# motor_controller.net
KiCad netlist of a schematic drawn in EAGLE
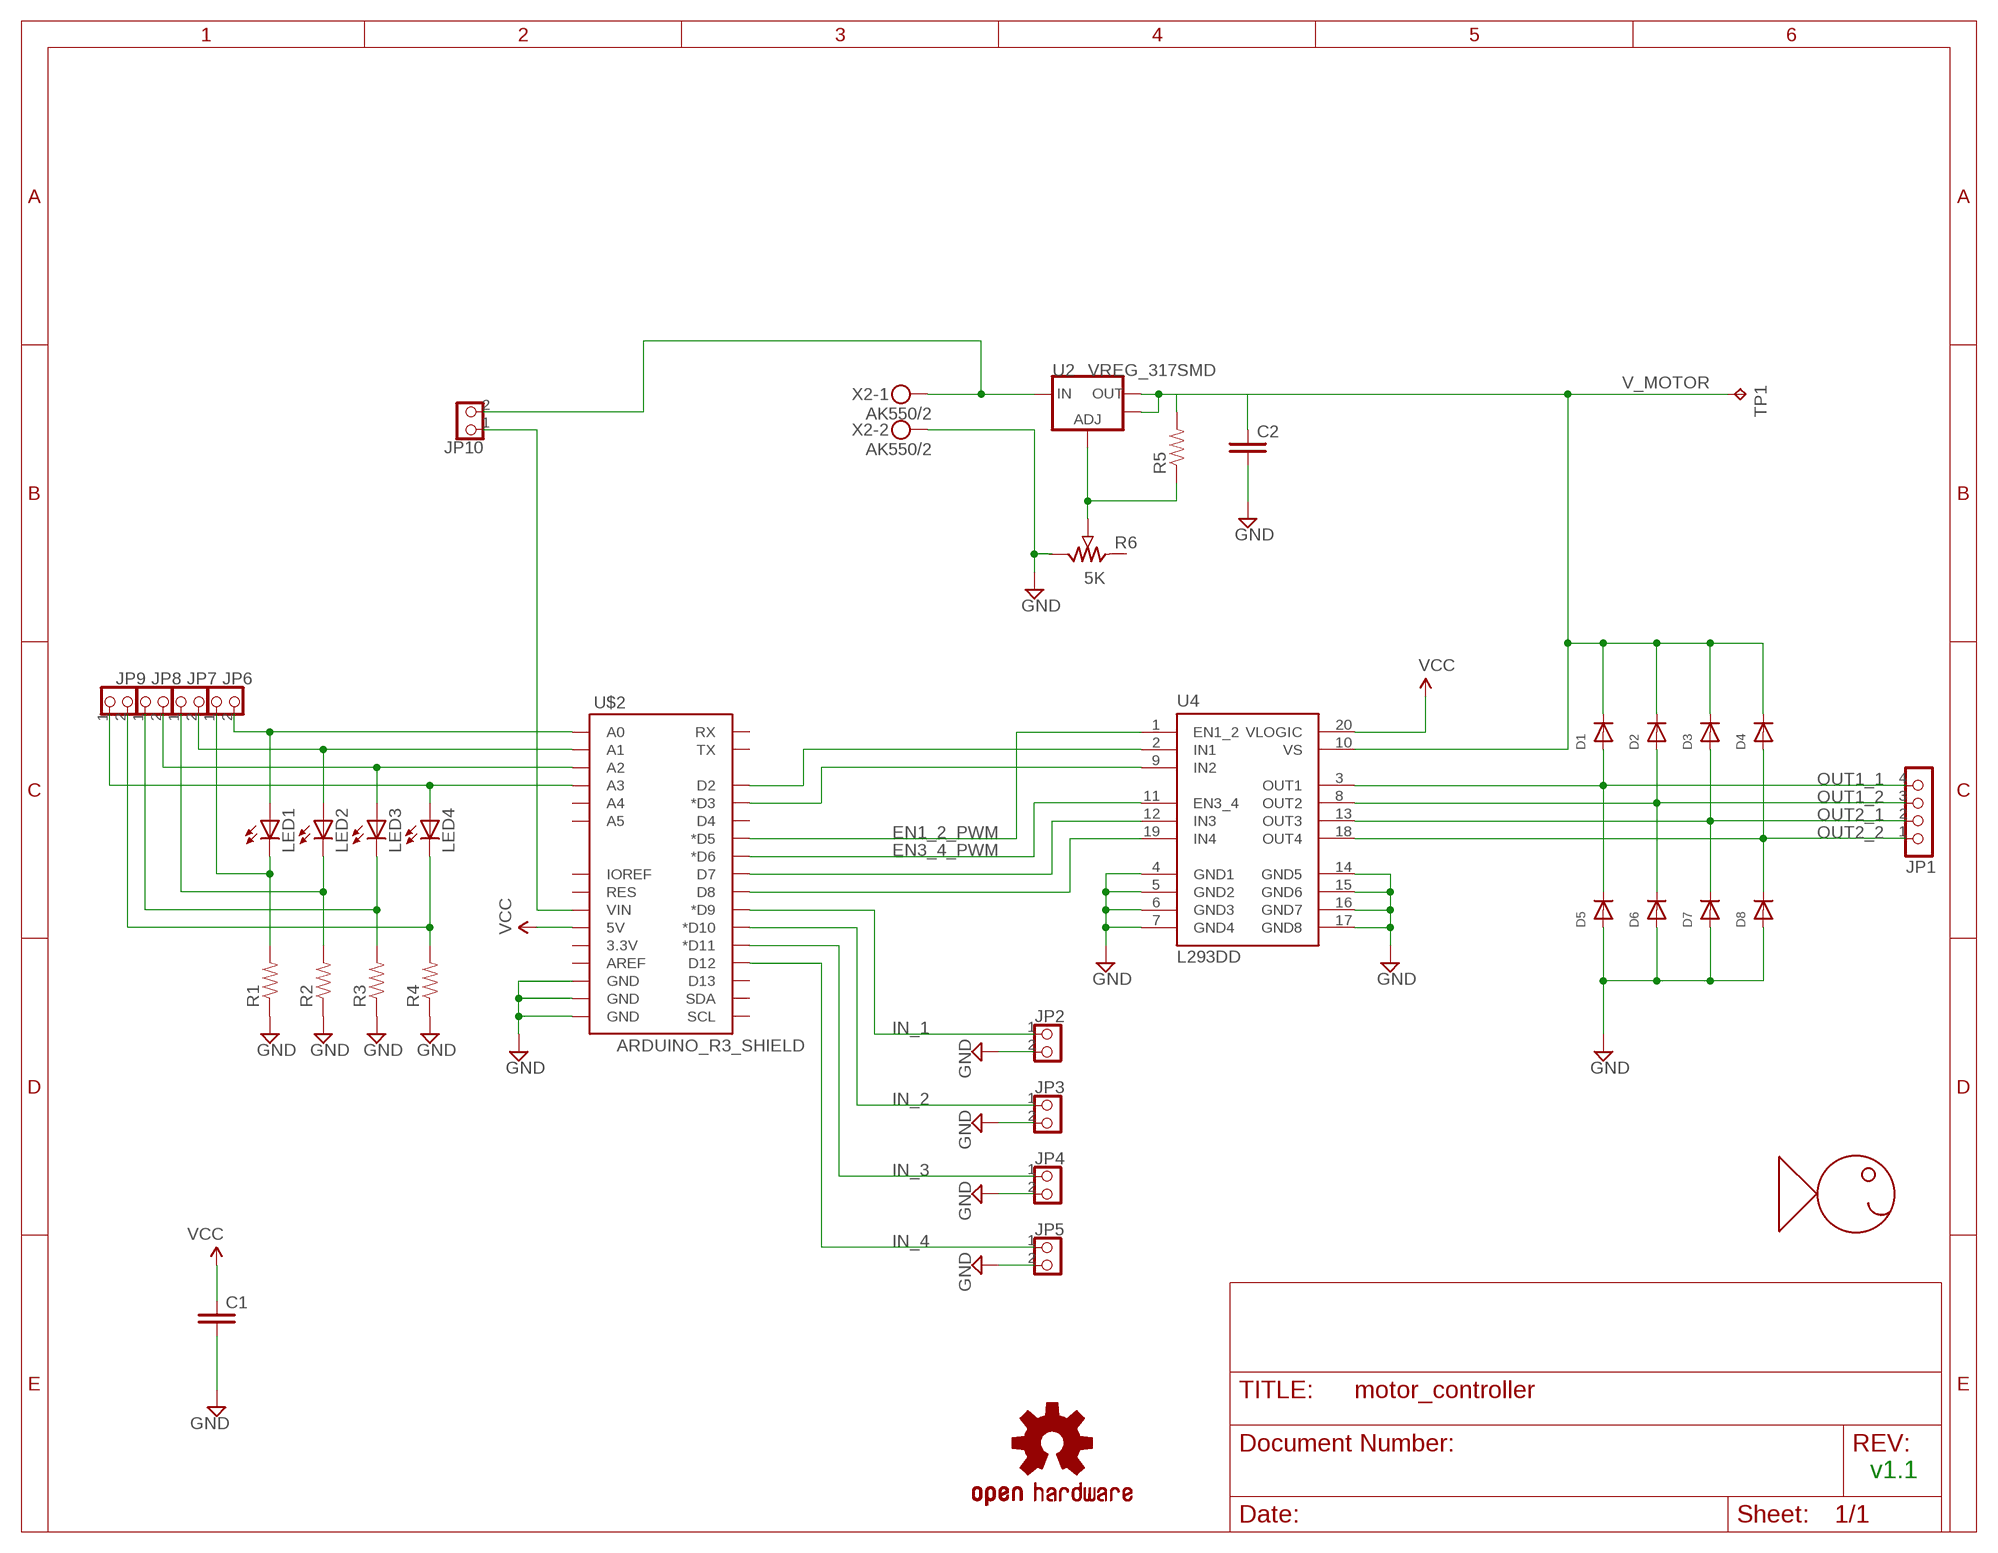
[diagram p0: schematic, sheet 1]

(export (version "E")
  (design (tool "Eeschema 10.0.6"))
  (components
    (comp (ref "C1")
      (value "CAPACITORC0603")
      (footprint "eagle-import:C0603")
      (libsource (lib "eagle-import") (part "CAPACITORC0603"))
    )
    (comp (ref "C2")
      (value "CAPACITORC0603")
      (footprint "eagle-import:C0603")
      (libsource (lib "eagle-import") (part "CAPACITORC0603"))
    )
    (comp (ref "D1")
      (value "DIODESOD-123")
      (footprint "eagle-import:SOD-123")
      (libsource (lib "eagle-import") (part "DIODESOD-123"))
    )
    (comp (ref "D2")
      (value "DIODESOD-123")
      (footprint "eagle-import:SOD-123")
      (libsource (lib "eagle-import") (part "DIODESOD-123"))
    )
    (comp (ref "D3")
      (value "DIODESOD-123")
      (footprint "eagle-import:SOD-123")
      (libsource (lib "eagle-import") (part "DIODESOD-123"))
    )
    (comp (ref "D4")
      (value "DIODESOD-123")
      (footprint "eagle-import:SOD-123")
      (libsource (lib "eagle-import") (part "DIODESOD-123"))
    )
    (comp (ref "D5")
      (value "DIODESOD-123")
      (footprint "eagle-import:SOD-123")
      (libsource (lib "eagle-import") (part "DIODESOD-123"))
    )
    (comp (ref "D6")
      (value "DIODESOD-123")
      (footprint "eagle-import:SOD-123")
      (libsource (lib "eagle-import") (part "DIODESOD-123"))
    )
    (comp (ref "D7")
      (value "DIODESOD-123")
      (footprint "eagle-import:SOD-123")
      (libsource (lib "eagle-import") (part "DIODESOD-123"))
    )
    (comp (ref "D8")
      (value "DIODESOD-123")
      (footprint "eagle-import:SOD-123")
      (libsource (lib "eagle-import") (part "DIODESOD-123"))
    )
    (comp (ref "JP1")
      (value "PINHD-1X4/90")
      (footprint "eagle-import:1X04_90")
      (libsource (lib "eagle-import") (part "PINHD-1X4/90"))
    )
    (comp (ref "JP2")
      (value "PINHD-1X2")
      (footprint "eagle-import:1X02")
      (libsource (lib "eagle-import") (part "PINHD-1X2"))
    )
    (comp (ref "JP3")
      (value "PINHD-1X2")
      (footprint "eagle-import:1X02")
      (libsource (lib "eagle-import") (part "PINHD-1X2"))
    )
    (comp (ref "JP4")
      (value "PINHD-1X2")
      (footprint "eagle-import:1X02")
      (libsource (lib "eagle-import") (part "PINHD-1X2"))
    )
    (comp (ref "JP5")
      (value "PINHD-1X2")
      (footprint "eagle-import:1X02")
      (libsource (lib "eagle-import") (part "PINHD-1X2"))
    )
    (comp (ref "JP6")
      (value "PINHD-1X2")
      (footprint "eagle-import:1X02")
      (libsource (lib "eagle-import") (part "PINHD-1X2"))
    )
    (comp (ref "JP7")
      (value "PINHD-1X2")
      (footprint "eagle-import:1X02")
      (libsource (lib "eagle-import") (part "PINHD-1X2"))
    )
    (comp (ref "JP8")
      (value "PINHD-1X2")
      (footprint "eagle-import:1X02")
      (libsource (lib "eagle-import") (part "PINHD-1X2"))
    )
    (comp (ref "JP9")
      (value "PINHD-1X2")
      (footprint "eagle-import:1X02")
      (libsource (lib "eagle-import") (part "PINHD-1X2"))
    )
    (comp (ref "JP10")
      (value "PINHD-1X2")
      (footprint "eagle-import:1X02")
      (libsource (lib "eagle-import") (part "PINHD-1X2"))
    )
    (comp (ref "LED1")
      (value "LED0805")
      (footprint "eagle-import:LED_0805")
      (libsource (lib "eagle-import") (part "LED0805"))
    )
    (comp (ref "LED2")
      (value "LED0805")
      (footprint "eagle-import:LED_0805")
      (libsource (lib "eagle-import") (part "LED0805"))
    )
    (comp (ref "LED3")
      (value "LED0805")
      (footprint "eagle-import:LED_0805")
      (libsource (lib "eagle-import") (part "LED0805"))
    )
    (comp (ref "LED4")
      (value "LED0805")
      (footprint "eagle-import:LED_0805")
      (libsource (lib "eagle-import") (part "LED0805"))
    )
    (comp (ref "LOGO1")
      (value "OSHW-LOGOM")
      (footprint "eagle-import:OSHW-LOGO-M")
      (libsource (lib "eagle-import") (part "OSHW-LOGOM"))
    )
    (comp (ref "R1")
      (value "RESISTOR_SMD0603-RES")
      (footprint "eagle-import:0603-RES")
      (libsource (lib "eagle-import") (part "RESISTOR_SMD0603-RES"))
    )
    (comp (ref "R2")
      (value "RESISTOR_SMD0603-RES")
      (footprint "eagle-import:0603-RES")
      (libsource (lib "eagle-import") (part "RESISTOR_SMD0603-RES"))
    )
    (comp (ref "R3")
      (value "RESISTOR_SMD0603-RES")
      (footprint "eagle-import:0603-RES")
      (libsource (lib "eagle-import") (part "RESISTOR_SMD0603-RES"))
    )
    (comp (ref "R4")
      (value "RESISTOR_SMD0603-RES")
      (footprint "eagle-import:0603-RES")
      (libsource (lib "eagle-import") (part "RESISTOR_SMD0603-RES"))
    )
    (comp (ref "R5")
      (value "RESISTOR_SMD0603-RES")
      (footprint "eagle-import:0603-RES")
      (libsource (lib "eagle-import") (part "RESISTOR_SMD0603-RES"))
    )
    (comp (ref "R6")
      (value "5K")
      (footprint "eagle-import:BOURNS_3362H")
      (libsource (lib "eagle-import") (part "POTBOURNS_3362H"))
    )
    (comp (ref "TP1")
      (value "TEST_POINTPAD1-20")
      (footprint "eagle-import:P1-20")
      (libsource (lib "eagle-import") (part "TEST_POINTPAD1-20"))
    )
    (comp (ref "U$1")
      (value "FHI_LOGO")
      (footprint "eagle-import:FHI_LOGO")
      (libsource (lib "eagle-import") (part "FHI_LOGO"))
    )
    (comp (ref "U$2")
      (value "ARDUINO_R3_SHIELD")
      (footprint "eagle-import:UNO_R3_SHIELD")
      (libsource (lib "eagle-import") (part "ARDUINO_R3_SHIELD"))
    )
    (comp (ref "U2")
      (value "VREG_317SMD")
      (footprint "eagle-import:SOT223")
      (libsource (lib "eagle-import") (part "VREG_317SMD"))
    )
    (comp (ref "U4")
      (value "L293DD")
      (footprint "eagle-import:SO20")
      (libsource (lib "eagle-import") (part "L293DD"))
    )
    (comp (ref "X2")
      (value "AK550/2")
      (footprint "eagle-import:AK550_2")
      (libsource (lib "eagle-import") (part "AK550/2"))
    )
  )
  (nets
    (net (code "1") (name "/EN1_2_PWM") (class "Default")
      (node (ref "U$2") (pin "D5") (pinfunction "*D5_D5") (pintype "bidirectional"))
      (node (ref "U4") (pin "1") (pinfunction "EN1_2_1") (pintype "input"))
    )
    (net (code "2") (name "/EN3_4_PWM") (class "Default")
      (node (ref "U$2") (pin "D6") (pinfunction "*D6_D6") (pintype "bidirectional"))
      (node (ref "U4") (pin "11") (pinfunction "EN3_4_11") (pintype "input"))
    )
    (net (code "3") (name "/IN_1") (class "Default")
      (node (ref "JP2") (pin "1") (pinfunction "1_1") (pintype "passive"))
      (node (ref "U$2") (pin "D9") (pinfunction "*D9_D9") (pintype "bidirectional"))
    )
    (net (code "4") (name "/IN_2") (class "Default")
      (node (ref "JP3") (pin "1") (pinfunction "1_1") (pintype "passive"))
      (node (ref "U$2") (pin "D10") (pinfunction "*D10_D10") (pintype "bidirectional"))
    )
    (net (code "5") (name "/IN_3") (class "Default")
      (node (ref "JP4") (pin "1") (pinfunction "1_1") (pintype "passive"))
      (node (ref "U$2") (pin "D11") (pinfunction "*D11_D11") (pintype "bidirectional"))
    )
    (net (code "6") (name "/IN_4") (class "Default")
      (node (ref "JP5") (pin "1") (pinfunction "1_1") (pintype "passive"))
      (node (ref "U$2") (pin "D12") (pinfunction "D12_D12") (pintype "bidirectional"))
    )
    (net (code "7") (name "/OUT1_1") (class "Default")
      (node (ref "D1") (pin "A") (pinfunction "A_A") (pintype "passive"))
      (node (ref "D5") (pin "C") (pinfunction "C_C") (pintype "passive"))
      (node (ref "JP1") (pin "4") (pinfunction "4_4") (pintype "passive"))
      (node (ref "U4") (pin "3") (pinfunction "OUT1_3") (pintype "output"))
    )
    (net (code "8") (name "/OUT1_2") (class "Default")
      (node (ref "D2") (pin "A") (pinfunction "A_A") (pintype "passive"))
      (node (ref "D6") (pin "C") (pinfunction "C_C") (pintype "passive"))
      (node (ref "JP1") (pin "3") (pinfunction "3_3") (pintype "passive"))
      (node (ref "U4") (pin "8") (pinfunction "OUT2_8") (pintype "output"))
    )
    (net (code "9") (name "/OUT2_1") (class "Default")
      (node (ref "D3") (pin "A") (pinfunction "A_A") (pintype "passive"))
      (node (ref "D7") (pin "C") (pinfunction "C_C") (pintype "passive"))
      (node (ref "JP1") (pin "2") (pinfunction "2_2") (pintype "passive"))
      (node (ref "U4") (pin "13") (pinfunction "OUT3_13") (pintype "output"))
    )
    (net (code "10") (name "/OUT2_2") (class "Default")
      (node (ref "D4") (pin "A") (pinfunction "A_A") (pintype "passive"))
      (node (ref "D8") (pin "C") (pinfunction "C_C") (pintype "passive"))
      (node (ref "JP1") (pin "1") (pinfunction "1_1") (pintype "passive"))
      (node (ref "U4") (pin "18") (pinfunction "OUT4_18") (pintype "output"))
    )
    (net (code "11") (name "/V_MOTOR") (class "Default")
      (node (ref "C2") (pin "1") (pinfunction "1_1") (pintype "passive"))
      (node (ref "D1") (pin "C") (pinfunction "C_C") (pintype "passive"))
      (node (ref "D2") (pin "C") (pinfunction "C_C") (pintype "passive"))
      (node (ref "D3") (pin "C") (pinfunction "C_C") (pintype "passive"))
      (node (ref "D4") (pin "C") (pinfunction "C_C") (pintype "passive"))
      (node (ref "R5") (pin "2") (pinfunction "2_2") (pintype "passive"))
      (node (ref "TP1") (pin "TP") (pinfunction "TP_TP") (pintype "input"))
      (node (ref "U2") (pin "2") (pinfunction "OUT1_2") (pintype "output"))
      (node (ref "U2") (pin "4") (pinfunction "OUT2_4") (pintype "output"))
      (node (ref "U4") (pin "10") (pinfunction "VS_10") (pintype "power_in"))
    )
    (net (code "12") (name "GND") (class "Default")
      (node (ref "C1") (pin "2") (pinfunction "2_2") (pintype "passive"))
      (node (ref "C2") (pin "2") (pinfunction "2_2") (pintype "passive"))
      (node (ref "D5") (pin "A") (pinfunction "A_A") (pintype "passive"))
      (node (ref "D6") (pin "A") (pinfunction "A_A") (pintype "passive"))
      (node (ref "D7") (pin "A") (pinfunction "A_A") (pintype "passive"))
      (node (ref "D8") (pin "A") (pinfunction "A_A") (pintype "passive"))
      (node (ref "JP2") (pin "2") (pinfunction "2_2") (pintype "passive"))
      (node (ref "JP3") (pin "2") (pinfunction "2_2") (pintype "passive"))
      (node (ref "JP4") (pin "2") (pinfunction "2_2") (pintype "passive"))
      (node (ref "JP5") (pin "2") (pinfunction "2_2") (pintype "passive"))
      (node (ref "R1") (pin "1") (pinfunction "1_1") (pintype "passive"))
      (node (ref "R2") (pin "1") (pinfunction "1_1") (pintype "passive"))
      (node (ref "R3") (pin "1") (pinfunction "1_1") (pintype "passive"))
      (node (ref "R4") (pin "1") (pinfunction "1_1") (pintype "passive"))
      (node (ref "R6") (pin "3") (pinfunction "3_3") (pintype "passive"))
      (node (ref "U$2") (pin "GND@0") (pinfunction "GND_GND@0") (pintype "bidirectional"))
      (node (ref "U$2") (pin "GND@1") (pinfunction "GND_GND@1") (pintype "bidirectional"))
      (node (ref "U$2") (pin "GND@2") (pinfunction "GND_GND@2") (pintype "bidirectional"))
      (node (ref "U4") (pin "14") (pinfunction "GND5_14") (pintype "power_in"))
      (node (ref "U4") (pin "15") (pinfunction "GND6_15") (pintype "power_in"))
      (node (ref "U4") (pin "16") (pinfunction "GND7_16") (pintype "power_in"))
      (node (ref "U4") (pin "17") (pinfunction "GND8_17") (pintype "power_in"))
      (node (ref "U4") (pin "4") (pinfunction "GND1_4") (pintype "power_in"))
      (node (ref "U4") (pin "5") (pinfunction "GND2_5") (pintype "power_in"))
      (node (ref "U4") (pin "6") (pinfunction "GND3_6") (pintype "power_in"))
      (node (ref "U4") (pin "7") (pinfunction "GND4_7") (pintype "power_in"))
      (node (ref "X2") (pin "2") (pinfunction "KL_2") (pintype "passive"))
    )
    (net (code "13") (name "Net-(JP6-Pad1)") (class "Default")
      (node (ref "JP6") (pin "1") (pinfunction "1_1") (pintype "passive"))
      (node (ref "LED1") (pin "C") (pinfunction "C_C") (pintype "passive"))
      (node (ref "R1") (pin "2") (pinfunction "2_2") (pintype "passive"))
    )
    (net (code "14") (name "Net-(JP6-Pad2)") (class "Default")
      (node (ref "JP6") (pin "2") (pinfunction "2_2") (pintype "passive"))
      (node (ref "LED1") (pin "A") (pinfunction "A_A") (pintype "passive"))
      (node (ref "U$2") (pin "A0") (pinfunction "A0_A0") (pintype "bidirectional"))
    )
    (net (code "15") (name "Net-(JP7-Pad1)") (class "Default")
      (node (ref "JP7") (pin "1") (pinfunction "1_1") (pintype "passive"))
      (node (ref "LED2") (pin "C") (pinfunction "C_C") (pintype "passive"))
      (node (ref "R2") (pin "2") (pinfunction "2_2") (pintype "passive"))
    )
    (net (code "16") (name "Net-(JP7-Pad2)") (class "Default")
      (node (ref "JP7") (pin "2") (pinfunction "2_2") (pintype "passive"))
      (node (ref "LED2") (pin "A") (pinfunction "A_A") (pintype "passive"))
      (node (ref "U$2") (pin "A1") (pinfunction "A1_A1") (pintype "bidirectional"))
    )
    (net (code "17") (name "Net-(JP8-Pad1)") (class "Default")
      (node (ref "JP8") (pin "1") (pinfunction "1_1") (pintype "passive"))
      (node (ref "LED3") (pin "C") (pinfunction "C_C") (pintype "passive"))
      (node (ref "R3") (pin "2") (pinfunction "2_2") (pintype "passive"))
    )
    (net (code "18") (name "Net-(JP8-Pad2)") (class "Default")
      (node (ref "JP8") (pin "2") (pinfunction "2_2") (pintype "passive"))
      (node (ref "LED3") (pin "A") (pinfunction "A_A") (pintype "passive"))
      (node (ref "U$2") (pin "A2") (pinfunction "A2_A2") (pintype "bidirectional"))
    )
    (net (code "19") (name "Net-(JP9-Pad1)") (class "Default")
      (node (ref "JP9") (pin "1") (pinfunction "1_1") (pintype "passive"))
      (node (ref "LED4") (pin "A") (pinfunction "A_A") (pintype "passive"))
      (node (ref "U$2") (pin "A3") (pinfunction "A3_A3") (pintype "bidirectional"))
    )
    (net (code "20") (name "Net-(JP9-Pad2)") (class "Default")
      (node (ref "JP9") (pin "2") (pinfunction "2_2") (pintype "passive"))
      (node (ref "LED4") (pin "C") (pinfunction "C_C") (pintype "passive"))
      (node (ref "R4") (pin "2") (pinfunction "2_2") (pintype "passive"))
    )
    (net (code "21") (name "Net-(JP10-Pad1)") (class "Default")
      (node (ref "JP10") (pin "1") (pinfunction "1_1") (pintype "passive"))
      (node (ref "U$2") (pin "VIN") (pinfunction "VIN_VIN") (pintype "bidirectional"))
    )
    (net (code "22") (name "Net-(U$2-*D3)") (class "Default")
      (node (ref "U$2") (pin "D3") (pinfunction "*D3_D3") (pintype "bidirectional"))
      (node (ref "U4") (pin "9") (pinfunction "IN2_9") (pintype "input"))
    )
    (net (code "23") (name "Net-(U2-ADJ)") (class "Default")
      (node (ref "R5") (pin "1") (pinfunction "1_1") (pintype "passive"))
      (node (ref "R6") (pin "2") (pinfunction "2_2") (pintype "passive"))
      (node (ref "U2") (pin "1") (pinfunction "ADJ_1") (pintype "input"))
    )
    (net (code "24") (name "Net-(U2-IN)") (class "Default")
      (node (ref "JP10") (pin "2") (pinfunction "2_2") (pintype "passive"))
      (node (ref "U2") (pin "3") (pinfunction "IN_3") (pintype "input"))
      (node (ref "X2") (pin "1") (pinfunction "KL_1") (pintype "passive"))
    )
    (net (code "25") (name "Net-(U4-IN1)") (class "Default")
      (node (ref "U$2") (pin "D2") (pinfunction "D2_D2") (pintype "bidirectional"))
      (node (ref "U4") (pin "2") (pinfunction "IN1_2") (pintype "input"))
    )
    (net (code "26") (name "Net-(U4-IN3)") (class "Default")
      (node (ref "U$2") (pin "D7") (pinfunction "D7_D7") (pintype "bidirectional"))
      (node (ref "U4") (pin "12") (pinfunction "IN3_12") (pintype "input"))
    )
    (net (code "27") (name "Net-(U4-IN4)") (class "Default")
      (node (ref "U$2") (pin "D8") (pinfunction "D8_D8") (pintype "bidirectional"))
      (node (ref "U4") (pin "19") (pinfunction "IN4_19") (pintype "input"))
    )
    (net (code "28") (name "VCC") (class "Default")
      (node (ref "C1") (pin "1") (pinfunction "1_1") (pintype "passive"))
      (node (ref "U$2") (pin "5V") (pinfunction "5V_5V") (pintype "bidirectional"))
      (node (ref "U4") (pin "20") (pinfunction "VLOGIC_20") (pintype "power_in"))
    )
    (net (code "29") (name "unconnected-(R6-Pad1)") (class "Default")
      (node (ref "R6") (pin "1") (pinfunction "1_1") (pintype "passive"))
    )
    (net (code "30") (name "unconnected-(U$2-Pad3.3V)") (class "Default")
      (node (ref "U$2") (pin "3.3V") (pinfunction "3.3V_3.3V") (pintype "bidirectional"))
    )
    (net (code "31") (name "unconnected-(U$2-PadA4)") (class "Default")
      (node (ref "U$2") (pin "A4") (pinfunction "A4_A4") (pintype "bidirectional"))
    )
    (net (code "32") (name "unconnected-(U$2-PadA5)") (class "Default")
      (node (ref "U$2") (pin "A5") (pinfunction "A5_A5") (pintype "bidirectional"))
    )
    (net (code "33") (name "unconnected-(U$2-PadAREF)") (class "Default")
      (node (ref "U$2") (pin "AREF") (pinfunction "AREF_AREF") (pintype "bidirectional"))
    )
    (net (code "34") (name "unconnected-(U$2-PadD4)") (class "Default")
      (node (ref "U$2") (pin "D4") (pinfunction "D4_D4") (pintype "bidirectional"))
    )
    (net (code "35") (name "unconnected-(U$2-PadD13)") (class "Default")
      (node (ref "U$2") (pin "D13") (pinfunction "D13_D13") (pintype "bidirectional"))
    )
    (net (code "36") (name "unconnected-(U$2-PadIOREF)") (class "Default")
      (node (ref "U$2") (pin "IOREF") (pinfunction "IOREF_IOREF") (pintype "bidirectional"))
    )
    (net (code "37") (name "unconnected-(U$2-PadRES)") (class "Default")
      (node (ref "U$2") (pin "RES") (pinfunction "RES_RES") (pintype "bidirectional"))
    )
    (net (code "38") (name "unconnected-(U$2-PadRX)") (class "Default")
      (node (ref "U$2") (pin "RX") (pinfunction "RX_RX") (pintype "bidirectional"))
    )
    (net (code "39") (name "unconnected-(U$2-PadSCL)") (class "Default")
      (node (ref "U$2") (pin "SCL") (pinfunction "SCL_SCL") (pintype "bidirectional"))
    )
    (net (code "40") (name "unconnected-(U$2-PadSDA)") (class "Default")
      (node (ref "U$2") (pin "SDA") (pinfunction "SDA_SDA") (pintype "bidirectional"))
    )
    (net (code "41") (name "unconnected-(U$2-PadTX)") (class "Default")
      (node (ref "U$2") (pin "TX") (pinfunction "TX_TX") (pintype "bidirectional"))
    )
  )
)
